# USB_TO_TTL.net
KiCad netlist of a schematic drawn in Altium Designer
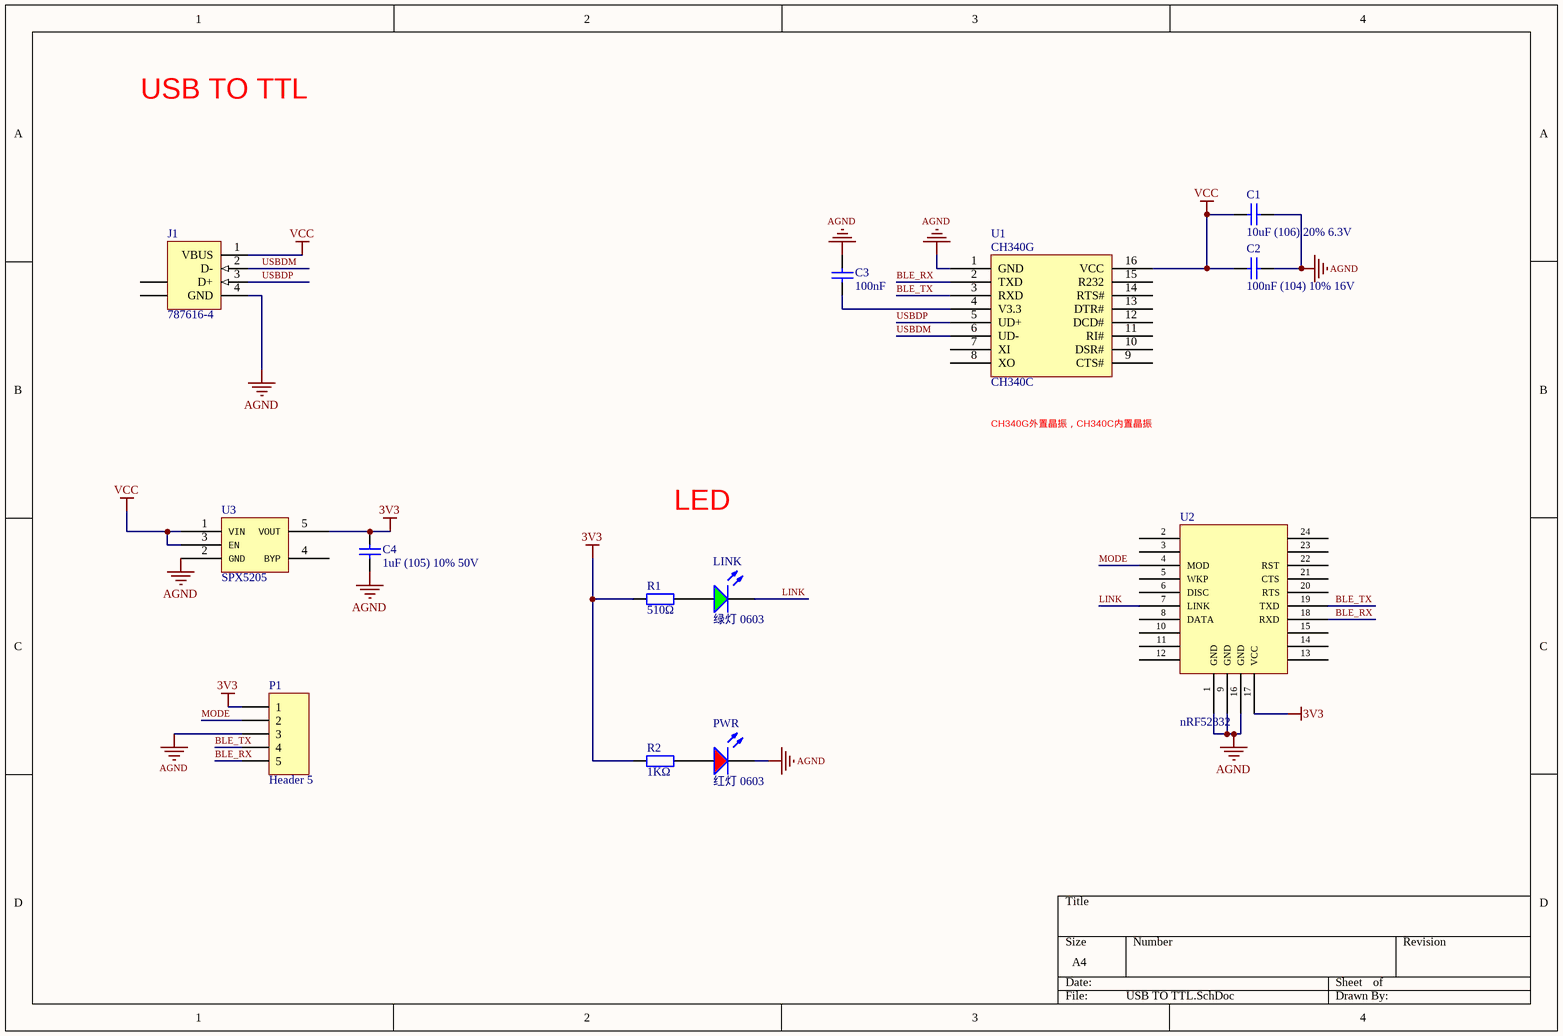
[diagram p0: USB TO TTL.SchDoc]

(export (version "E")
  (design (tool "Eeschema 10.0.6"))
  (components
    (comp (ref "C1")
      (value "10uF (106) 20% 6.3V")
      (footprint "0603_C")
      (description "贴片电容")
      (libsource (lib "Miscellaneous Devices LC") (part "0402 10uF (106) 20% 6.3V"))
    )
    (comp (ref "C2")
      (value "100nF (104) 10% 16V")
      (footprint "0603_C")
      (description "贴片电容")
      (libsource (lib "Miscellaneous Devices LC") (part "0402 100nF (104) 10% 16V"))
    )
    (comp (ref "C3")
      (value "100nF")
      (footprint "0603_C")
      (description "贴片电容")
      (libsource (lib "Miscellaneous Devices LC") (part "0402 100nF (104) 10% 16V"))
    )
    (comp (ref "C4")
      (value "1uF (105) 10% 50V")
      (footprint "0603_C")
      (description "贴片电容")
      (libsource (lib "Miscellaneous Devices LC") (part "0603 1uF (105) 10% 50V"))
    )
    (comp (ref "J1")
      (value "787616-4")
      (footprint "USB-A直插公头")
      (description "USB 1.1, Right Angle, Thru-Hole, A Type, Receptacle, 4 Position, Black")
      (fields (field (name "PUBLISHER") "Altium Limited"))
      (libsource (lib "AMP Serial Bus USB") (part "787616-4"))
    )
    (comp (ref "LINK")
      (value "绿灯 0603")
      (footprint "0603_LED_S1")
      (description "发光二极管")
      (libsource (lib "Miscellaneous Devices LC") (part "0603 绿灯"))
    )
    (comp (ref "P1")
      (value "Header 5")
      (footprint "HDR1X5")
      (description "Header, 5-Pin")
      (fields (field (name "PUBLISHER") "Altium Limited"))
      (libsource (lib "Miscellaneous Connectors") (part "Header 5"))
    )
    (comp (ref "PWR")
      (value "红灯 0603")
      (footprint "0603_LED_S1")
      (description "发光二极管")
      (libsource (lib "Miscellaneous Devices LC") (part "0603 红灯"))
    )
    (comp (ref "R1")
      (value "510Ω")
      (footprint "0603_R")
      (description "贴片电阻")
      (libsource (lib "Miscellaneous Devices LC") (part "0603 510Ω (5100) 1%"))
    )
    (comp (ref "R2")
      (value "1KΩ")
      (footprint "0603_R")
      (description "贴片电阻")
      (libsource (lib "Miscellaneous Devices LC") (part "0603 1KΩ (1001) 1%"))
    )
    (comp (ref "U1")
      (value "CH340C")
      (footprint "SOIC-16_150mil")
      (description "USB")
      (libsource (lib "TI Voltage Controlled Oscillator") (part "CH340G_[C14267]"))
    )
    (comp (ref "U2") (value "nRF52832") (footprint "nRF52832") (libsource (lib "EEG") (part "nRF52832")))
    (comp (ref "U3") (value "SPX5205") (footprint "SOT-23-5") (libsource (lib "EEG") (part "SPX5205")))
  )
  (nets
    (net (code "1") (name "/BLE_RX") (class "Default")
      (node (ref "P1") (pin "5") (pinfunction "5_5") (pintype "passive"))
      (node (ref "U1") (pin "2") (pinfunction "TXD_2") (pintype "passive"))
      (node (ref "U2") (pin "18") (pinfunction "RXD_18") (pintype "passive"))
    )
    (net (code "2") (name "/BLE_TX") (class "Default")
      (node (ref "P1") (pin "4") (pinfunction "4_4") (pintype "passive"))
      (node (ref "U1") (pin "3") (pinfunction "RXD_3") (pintype "passive"))
      (node (ref "U2") (pin "19") (pinfunction "TXD_19") (pintype "passive"))
    )
    (net (code "3") (name "/LINK") (class "Default")
      (node (ref "LINK") (pin "K") (pinfunction "K_K") (pintype "passive"))
      (node (ref "U2") (pin "7") (pinfunction "LINK_7") (pintype "passive"))
    )
    (net (code "4") (name "/MODE") (class "Default")
      (node (ref "P1") (pin "2") (pinfunction "2_2") (pintype "passive"))
      (node (ref "U2") (pin "4") (pinfunction "MOD_4") (pintype "passive"))
    )
    (net (code "5") (name "/USBDM") (class "Default")
      (node (ref "J1") (pin "2") (pinfunction "D-_2") (pintype "input"))
      (node (ref "U1") (pin "6") (pinfunction "UD-_6") (pintype "passive"))
    )
    (net (code "6") (name "/USBDP") (class "Default")
      (node (ref "J1") (pin "3") (pinfunction "D+_3") (pintype "input"))
      (node (ref "U1") (pin "5") (pinfunction "UD+_5") (pintype "passive"))
    )
    (net (code "7") (name "3V3") (class "Default")
      (node (ref "C4") (pin "2") (pinfunction "2_2") (pintype "passive"))
      (node (ref "P1") (pin "1") (pinfunction "1_1") (pintype "passive"))
      (node (ref "R1") (pin "1") (pinfunction "1_1") (pintype "passive"))
      (node (ref "R2") (pin "1") (pinfunction "1_1") (pintype "passive"))
      (node (ref "U2") (pin "17") (pinfunction "VCC_17") (pintype "passive"))
      (node (ref "U3") (pin "5") (pinfunction "VOUT_5") (pintype "passive"))
    )
    (net (code "8") (name "AGND") (class "Default")
      (node (ref "C1") (pin "2") (pinfunction "2_2") (pintype "passive"))
      (node (ref "C2") (pin "2") (pinfunction "2_2") (pintype "passive"))
      (node (ref "C3") (pin "2") (pinfunction "2_2") (pintype "passive"))
      (node (ref "C4") (pin "1") (pinfunction "1_1") (pintype "passive"))
      (node (ref "J1") (pin "4") (pinfunction "GND_4") (pintype "power_in"))
      (node (ref "P1") (pin "3") (pinfunction "3_3") (pintype "passive"))
      (node (ref "PWR") (pin "K") (pinfunction "K_K") (pintype "passive"))
      (node (ref "U1") (pin "1") (pinfunction "GND_1") (pintype "passive"))
      (node (ref "U2") (pin "1") (pinfunction "GND_1") (pintype "passive"))
      (node (ref "U2") (pin "16") (pinfunction "GND_16") (pintype "passive"))
      (node (ref "U2") (pin "9") (pinfunction "GND_9") (pintype "passive"))
      (node (ref "U3") (pin "2") (pinfunction "GND_2") (pintype "passive"))
    )
    (net (code "9") (name "Net-(LINK-PadA)") (class "Default")
      (node (ref "LINK") (pin "A") (pinfunction "A_A") (pintype "passive"))
      (node (ref "R1") (pin "2") (pinfunction "2_2") (pintype "passive"))
    )
    (net (code "10") (name "Net-(PWR-PadA)") (class "Default")
      (node (ref "PWR") (pin "A") (pinfunction "A_A") (pintype "passive"))
      (node (ref "R2") (pin "2") (pinfunction "2_2") (pintype "passive"))
    )
    (net (code "11") (name "Net-(U1-V3.3)") (class "Default")
      (node (ref "C3") (pin "1") (pinfunction "1_1") (pintype "passive"))
      (node (ref "U1") (pin "4") (pinfunction "V3.3_4") (pintype "passive"))
    )
    (net (code "12") (name "VCC") (class "Default")
      (node (ref "C1") (pin "1") (pinfunction "1_1") (pintype "passive"))
      (node (ref "C2") (pin "1") (pinfunction "1_1") (pintype "passive"))
      (node (ref "J1") (pin "1") (pinfunction "VBUS_1") (pintype "power_in"))
      (node (ref "U1") (pin "16") (pinfunction "VCC_16") (pintype "passive"))
      (node (ref "U3") (pin "1") (pinfunction "VIN_1") (pintype "passive"))
      (node (ref "U3") (pin "3") (pinfunction "EN_3") (pintype "passive"))
    )
    (net (code "13") (name "unconnected-(J1-SHLD-Pad5)") (class "Default")
      (node (ref "J1") (pin "5") (pinfunction "SHLD_5") (pintype "passive"))
    )
    (net (code "14") (name "unconnected-(J1-SHLD-Pad6)") (class "Default")
      (node (ref "J1") (pin "6") (pinfunction "SHLD_6") (pintype "passive"))
    )
    (net (code "15") (name "unconnected-(U1-CTS#-Pad9)") (class "Default")
      (node (ref "U1") (pin "9") (pinfunction "CTS#_9") (pintype "passive"))
    )
    (net (code "16") (name "unconnected-(U1-DCD#-Pad12)") (class "Default")
      (node (ref "U1") (pin "12") (pinfunction "DCD#_12") (pintype "passive"))
    )
    (net (code "17") (name "unconnected-(U1-DSR#-Pad10)") (class "Default")
      (node (ref "U1") (pin "10") (pinfunction "DSR#_10") (pintype "passive"))
    )
    (net (code "18") (name "unconnected-(U1-DTR#-Pad13)") (class "Default")
      (node (ref "U1") (pin "13") (pinfunction "DTR#_13") (pintype "passive"))
    )
    (net (code "19") (name "unconnected-(U1-R232-Pad15)") (class "Default")
      (node (ref "U1") (pin "15") (pinfunction "R232_15") (pintype "passive"))
    )
    (net (code "20") (name "unconnected-(U1-RI#-Pad11)") (class "Default")
      (node (ref "U1") (pin "11") (pinfunction "RI#_11") (pintype "passive"))
    )
    (net (code "21") (name "unconnected-(U1-RTS#-Pad14)") (class "Default")
      (node (ref "U1") (pin "14") (pinfunction "RTS#_14") (pintype "passive"))
    )
    (net (code "22") (name "unconnected-(U1-XI-Pad7)") (class "Default")
      (node (ref "U1") (pin "7") (pinfunction "XI_7") (pintype "passive"))
    )
    (net (code "23") (name "unconnected-(U1-XO-Pad8)") (class "Default")
      (node (ref "U1") (pin "8") (pinfunction "XO_8") (pintype "passive"))
    )
    (net (code "24") (name "unconnected-(U2-CTS-Pad21)") (class "Default")
      (node (ref "U2") (pin "21") (pinfunction "CTS_21") (pintype "passive"))
    )
    (net (code "25") (name "unconnected-(U2-DATA-Pad8)") (class "Default")
      (node (ref "U2") (pin "8") (pinfunction "DATA_8") (pintype "passive"))
    )
    (net (code "26") (name "unconnected-(U2-DISC-Pad6)") (class "Default")
      (node (ref "U2") (pin "6") (pinfunction "DISC_6") (pintype "passive"))
    )
    (net (code "27") (name "unconnected-(U2-Pad2)") (class "Default")
      (node (ref "U2") (pin "2") (pintype "passive"))
    )
    (net (code "28") (name "unconnected-(U2-Pad3)") (class "Default")
      (node (ref "U2") (pin "3") (pintype "passive"))
    )
    (net (code "29") (name "unconnected-(U2-Pad10)") (class "Default")
      (node (ref "U2") (pin "10") (pintype "passive"))
    )
    (net (code "30") (name "unconnected-(U2-Pad11)") (class "Default")
      (node (ref "U2") (pin "11") (pintype "passive"))
    )
    (net (code "31") (name "unconnected-(U2-Pad12)") (class "Default")
      (node (ref "U2") (pin "12") (pintype "passive"))
    )
    (net (code "32") (name "unconnected-(U2-Pad13)") (class "Default")
      (node (ref "U2") (pin "13") (pintype "passive"))
    )
    (net (code "33") (name "unconnected-(U2-Pad14)") (class "Default")
      (node (ref "U2") (pin "14") (pintype "passive"))
    )
    (net (code "34") (name "unconnected-(U2-Pad15)") (class "Default")
      (node (ref "U2") (pin "15") (pintype "passive"))
    )
    (net (code "35") (name "unconnected-(U2-Pad23)") (class "Default")
      (node (ref "U2") (pin "23") (pintype "passive"))
    )
    (net (code "36") (name "unconnected-(U2-Pad24)") (class "Default")
      (node (ref "U2") (pin "24") (pintype "passive"))
    )
    (net (code "37") (name "unconnected-(U2-RST-Pad22)") (class "Default")
      (node (ref "U2") (pin "22") (pinfunction "RST_22") (pintype "passive"))
    )
    (net (code "38") (name "unconnected-(U2-RTS-Pad20)") (class "Default")
      (node (ref "U2") (pin "20") (pinfunction "RTS_20") (pintype "passive"))
    )
    (net (code "39") (name "unconnected-(U2-WKP-Pad5)") (class "Default")
      (node (ref "U2") (pin "5") (pinfunction "WKP_5") (pintype "passive"))
    )
    (net (code "40") (name "unconnected-(U3-BYP-Pad4)") (class "Default")
      (node (ref "U3") (pin "4") (pinfunction "BYP_4") (pintype "passive"))
    )
  )
)
